# m901-vu-meter.net
KiCad netlist of a schematic drawn in EAGLE
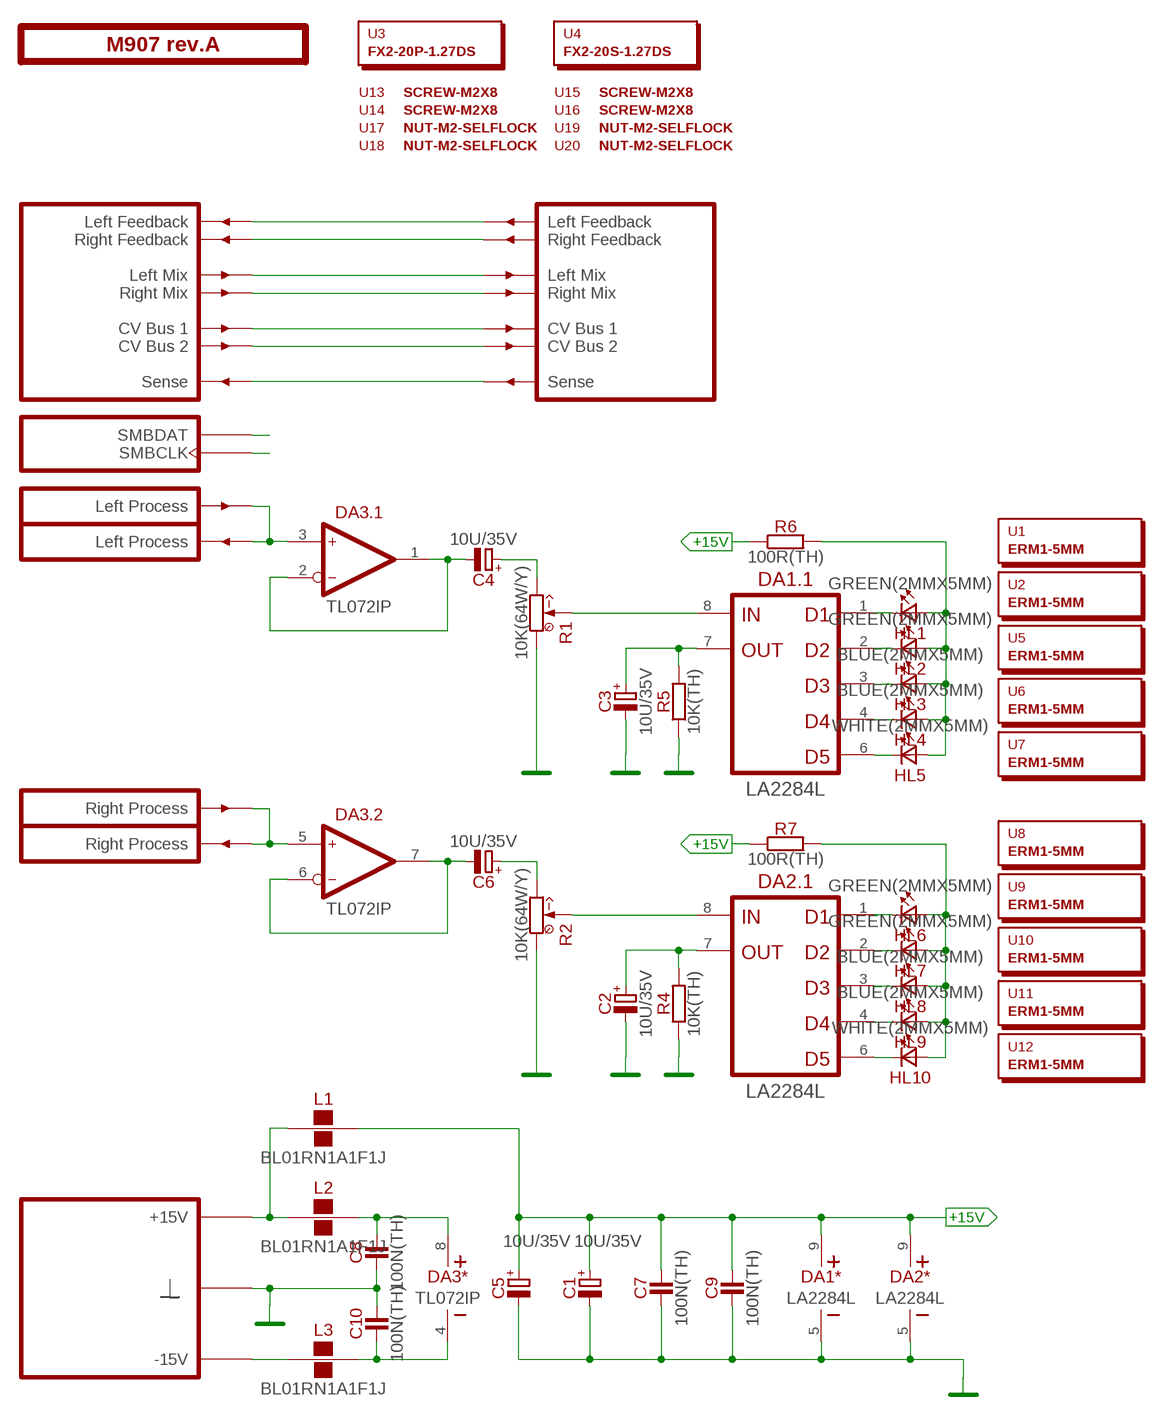
[diagram p0: schematic, sheet 1]

(export (version "E")
  (design (tool "Eeschema 10.0.6"))
  (components
    (comp (ref "C1")
      (value "10U/35V")
      (footprint "eagle-import:E2-5")
      (libsource (lib "eagle-import") (part "?10U/35V"))
    )
    (comp (ref "C2")
      (value "10U/35V")
      (footprint "eagle-import:E2-5")
      (libsource (lib "eagle-import") (part "?10U/35V"))
    )
    (comp (ref "C3")
      (value "10U/35V")
      (footprint "eagle-import:E2-5")
      (libsource (lib "eagle-import") (part "?10U/35V"))
    )
    (comp (ref "C4")
      (value "10U/35V")
      (footprint "eagle-import:E2-5")
      (libsource (lib "eagle-import") (part "?10U/35V"))
    )
    (comp (ref "C5")
      (value "10U/35V")
      (footprint "eagle-import:E2-5")
      (libsource (lib "eagle-import") (part "?10U/35V"))
    )
    (comp (ref "C6")
      (value "10U/35V")
      (footprint "eagle-import:E2-5")
      (libsource (lib "eagle-import") (part "?10U/35V"))
    )
    (comp (ref "C7")
      (value "100N(TH)")
      (footprint "eagle-import:C050-024X044")
      (libsource (lib "eagle-import") (part "?100N(TH)"))
    )
    (comp (ref "C8")
      (value "100N(TH)")
      (footprint "eagle-import:C050-024X044")
      (libsource (lib "eagle-import") (part "?100N(TH)"))
    )
    (comp (ref "C9")
      (value "100N(TH)")
      (footprint "eagle-import:C050-024X044")
      (libsource (lib "eagle-import") (part "?100N(TH)"))
    )
    (comp (ref "C10")
      (value "100N(TH)")
      (footprint "eagle-import:C050-024X044")
      (libsource (lib "eagle-import") (part "?100N(TH)"))
    )
    (comp (ref "DA1")
      (value "LA2284L")
      (footprint "eagle-import:SIL9")
      (libsource (lib "eagle-import") (part "LA2284L"))
    )
    (comp (ref "DA2")
      (value "LA2284L")
      (footprint "eagle-import:SIL9")
      (libsource (lib "eagle-import") (part "LA2284L"))
    )
    (comp (ref "DA3")
      (value "TL072IP")
      (footprint "eagle-import:DIP-8")
      (libsource (lib "eagle-import") (part "TL072IP"))
    )
    (comp (ref "HL1")
      (value "GREEN(2MMX5MM)")
      (footprint "eagle-import:LED2X5")
      (libsource (lib "eagle-import") (part "?(2MMX5MM)GREEN"))
    )
    (comp (ref "HL2")
      (value "GREEN(2MMX5MM)")
      (footprint "eagle-import:LED2X5")
      (libsource (lib "eagle-import") (part "?(2MMX5MM)GREEN"))
    )
    (comp (ref "HL3")
      (value "BLUE(2MMX5MM)")
      (footprint "eagle-import:LED2X5")
      (libsource (lib "eagle-import") (part "?(2MMX5MM)BLUE"))
    )
    (comp (ref "HL4")
      (value "BLUE(2MMX5MM)")
      (footprint "eagle-import:LED2X5")
      (libsource (lib "eagle-import") (part "?(2MMX5MM)BLUE"))
    )
    (comp (ref "HL5")
      (value "WHITE(2MMX5MM)")
      (footprint "eagle-import:LED2X5")
      (libsource (lib "eagle-import") (part "?(2MMX5MM)WHITE"))
    )
    (comp (ref "HL6")
      (value "GREEN(2MMX5MM)")
      (footprint "eagle-import:LED2X5")
      (libsource (lib "eagle-import") (part "?(2MMX5MM)GREEN"))
    )
    (comp (ref "HL7")
      (value "GREEN(2MMX5MM)")
      (footprint "eagle-import:LED2X5")
      (libsource (lib "eagle-import") (part "?(2MMX5MM)GREEN"))
    )
    (comp (ref "HL8")
      (value "BLUE(2MMX5MM)")
      (footprint "eagle-import:LED2X5")
      (libsource (lib "eagle-import") (part "?(2MMX5MM)BLUE"))
    )
    (comp (ref "HL9")
      (value "BLUE(2MMX5MM)")
      (footprint "eagle-import:LED2X5")
      (libsource (lib "eagle-import") (part "?(2MMX5MM)BLUE"))
    )
    (comp (ref "HL10")
      (value "WHITE(2MMX5MM)")
      (footprint "eagle-import:LED2X5")
      (libsource (lib "eagle-import") (part "?(2MMX5MM)WHITE"))
    )
    (comp (ref "L1")
      (value "BL01RN1A1F1J")
      (footprint "eagle-import:BL01RN1A")
      (libsource (lib "eagle-import") (part "BL01RN1A?1F1J"))
    )
    (comp (ref "L2")
      (value "BL01RN1A1F1J")
      (footprint "eagle-import:BL01RN1A")
      (libsource (lib "eagle-import") (part "BL01RN1A?1F1J"))
    )
    (comp (ref "L3")
      (value "BL01RN1A1F1J")
      (footprint "eagle-import:BL01RN1A")
      (libsource (lib "eagle-import") (part "BL01RN1A?1F1J"))
    )
    (comp (ref "PCB1")
      (value "M907 rev.A")
      (footprint "eagle-import:ST2-BOARD-26")
      (libsource (lib "eagle-import") (part "ST2-BOARD-?26"))
    )
    (comp (ref "R1")
      (value "10K(64W/Y)")
      (footprint "eagle-import:64W")
      (libsource (lib "eagle-import") (part "?(64W/Y)10K"))
    )
    (comp (ref "R2")
      (value "10K(64W/Y)")
      (footprint "eagle-import:64W")
      (libsource (lib "eagle-import") (part "?(64W/Y)10K"))
    )
    (comp (ref "R4")
      (value "10K(TH)")
      (footprint "eagle-import:R-0207_10")
      (libsource (lib "eagle-import") (part "?10K(TH)"))
    )
    (comp (ref "R5")
      (value "10K(TH)")
      (footprint "eagle-import:R-0207_10")
      (libsource (lib "eagle-import") (part "?10K(TH)"))
    )
    (comp (ref "R6")
      (value "100R(TH)")
      (footprint "eagle-import:R-0207_10")
      (libsource (lib "eagle-import") (part "?100R(TH)"))
    )
    (comp (ref "R7")
      (value "100R(TH)")
      (footprint "eagle-import:R-0207_10")
      (libsource (lib "eagle-import") (part "?100R(TH)"))
    )
    (comp (ref "U1")
      (value "ERM1-5MM")
      (footprint "eagle-import:EMPTY")
      (libsource (lib "eagle-import") (part "?ERM1-5MM"))
    )
    (comp (ref "U2")
      (value "ERM1-5MM")
      (footprint "eagle-import:EMPTY")
      (libsource (lib "eagle-import") (part "?ERM1-5MM"))
    )
    (comp (ref "U3")
      (value "FX2-20P-1.27DS")
      (footprint "eagle-import:EMPTY")
      (libsource (lib "eagle-import") (part "?FX2-20P-1.27DS"))
    )
    (comp (ref "U4")
      (value "FX2-20S-1.27DS")
      (footprint "eagle-import:EMPTY")
      (libsource (lib "eagle-import") (part "?FX2-20S-1.27DS"))
    )
    (comp (ref "U5")
      (value "ERM1-5MM")
      (footprint "eagle-import:EMPTY")
      (libsource (lib "eagle-import") (part "?ERM1-5MM"))
    )
    (comp (ref "U6")
      (value "ERM1-5MM")
      (footprint "eagle-import:EMPTY")
      (libsource (lib "eagle-import") (part "?ERM1-5MM"))
    )
    (comp (ref "U7")
      (value "ERM1-5MM")
      (footprint "eagle-import:EMPTY")
      (libsource (lib "eagle-import") (part "?ERM1-5MM"))
    )
    (comp (ref "U8")
      (value "ERM1-5MM")
      (footprint "eagle-import:EMPTY")
      (libsource (lib "eagle-import") (part "?ERM1-5MM"))
    )
    (comp (ref "U9")
      (value "ERM1-5MM")
      (footprint "eagle-import:EMPTY")
      (libsource (lib "eagle-import") (part "?ERM1-5MM"))
    )
    (comp (ref "U10")
      (value "ERM1-5MM")
      (footprint "eagle-import:EMPTY")
      (libsource (lib "eagle-import") (part "?ERM1-5MM"))
    )
    (comp (ref "U11")
      (value "ERM1-5MM")
      (footprint "eagle-import:EMPTY")
      (libsource (lib "eagle-import") (part "?ERM1-5MM"))
    )
    (comp (ref "U12")
      (value "ERM1-5MM")
      (footprint "eagle-import:EMPTY")
      (libsource (lib "eagle-import") (part "?ERM1-5MM"))
    )
    (comp (ref "U13")
      (value "SCREW-M2X8")
      (footprint "eagle-import:EMPTY")
      (libsource (lib "eagle-import") (part "?SCREW-M2X8"))
    )
    (comp (ref "U14")
      (value "SCREW-M2X8")
      (footprint "eagle-import:EMPTY")
      (libsource (lib "eagle-import") (part "?SCREW-M2X8"))
    )
    (comp (ref "U15")
      (value "SCREW-M2X8")
      (footprint "eagle-import:EMPTY")
      (libsource (lib "eagle-import") (part "?SCREW-M2X8"))
    )
    (comp (ref "U16")
      (value "SCREW-M2X8")
      (footprint "eagle-import:EMPTY")
      (libsource (lib "eagle-import") (part "?SCREW-M2X8"))
    )
    (comp (ref "U17")
      (value "NUT-M2-SELFLOCK")
      (footprint "eagle-import:EMPTY")
      (libsource (lib "eagle-import") (part "?NUT-M2-SELFLOCK"))
    )
    (comp (ref "U18")
      (value "NUT-M2-SELFLOCK")
      (footprint "eagle-import:EMPTY")
      (libsource (lib "eagle-import") (part "?NUT-M2-SELFLOCK"))
    )
    (comp (ref "U19")
      (value "NUT-M2-SELFLOCK")
      (footprint "eagle-import:EMPTY")
      (libsource (lib "eagle-import") (part "?NUT-M2-SELFLOCK"))
    )
    (comp (ref "U20")
      (value "NUT-M2-SELFLOCK")
      (footprint "eagle-import:EMPTY")
      (libsource (lib "eagle-import") (part "?NUT-M2-SELFLOCK"))
    )
  )
  (nets
    (net (code "1") (name "+15V") (class "Default")
      (node (ref "C1") (pin "+") (pinfunction "+_+") (pintype "passive"))
      (node (ref "C5") (pin "+") (pinfunction "+_+") (pintype "passive"))
      (node (ref "C7") (pin "2") (pinfunction "2_2") (pintype "passive"))
      (node (ref "C9") (pin "2") (pinfunction "2_2") (pintype "passive"))
      (node (ref "DA1") (pin "9") (pinfunction "V+_9") (pintype "power_in"))
      (node (ref "DA2") (pin "9") (pinfunction "V+_9") (pintype "power_in"))
      (node (ref "L1") (pin "2") (pinfunction "2_2") (pintype "passive"))
      (node (ref "R6") (pin "1") (pinfunction "1_1") (pintype "passive"))
      (node (ref "R7") (pin "1") (pinfunction "1_1") (pintype "passive"))
    )
    (net (code "2") (name "GND") (class "Default")
      (node (ref "C1") (pin "-") (pinfunction "-_-") (pintype "passive"))
      (node (ref "C10") (pin "2") (pinfunction "2_2") (pintype "passive"))
      (node (ref "C2") (pin "-") (pinfunction "-_-") (pintype "passive"))
      (node (ref "C3") (pin "-") (pinfunction "-_-") (pintype "passive"))
      (node (ref "C5") (pin "-") (pinfunction "-_-") (pintype "passive"))
      (node (ref "C7") (pin "1") (pinfunction "1_1") (pintype "passive"))
      (node (ref "C8") (pin "1") (pinfunction "1_1") (pintype "passive"))
      (node (ref "C9") (pin "1") (pinfunction "1_1") (pintype "passive"))
      (node (ref "DA1") (pin "5") (pinfunction "V-_5") (pintype "power_in"))
      (node (ref "DA2") (pin "5") (pinfunction "V-_5") (pintype "power_in"))
      (node (ref "PCB1") (pin "B4") (pinfunction "GND_B4") (pintype "bidirectional"))
      (node (ref "PCB1") (pin "B4'") (pinfunction "GND_B4'") (pintype "bidirectional"))
      (node (ref "PCB1") (pin "B5") (pinfunction "GND_B5") (pintype "bidirectional"))
      (node (ref "PCB1") (pin "B5'") (pinfunction "GND_B5'") (pintype "bidirectional"))
      (node (ref "PCB1") (pin "B6") (pinfunction "GND_B6") (pintype "bidirectional"))
      (node (ref "PCB1") (pin "B6'") (pinfunction "GND_B6'") (pintype "bidirectional"))
      (node (ref "PCB1") (pin "B7") (pinfunction "GND_B7") (pintype "bidirectional"))
      (node (ref "PCB1") (pin "B7'") (pinfunction "GND_B7'") (pintype "bidirectional"))
      (node (ref "PCB1") (pin "B8") (pinfunction "GND_B8") (pintype "bidirectional"))
      (node (ref "PCB1") (pin "B8'") (pinfunction "GND_B8'") (pintype "bidirectional"))
      (node (ref "R1") (pin "1") (pinfunction "CCW_1") (pintype "passive"))
      (node (ref "R2") (pin "1") (pinfunction "CCW_1") (pintype "passive"))
      (node (ref "R4") (pin "1") (pinfunction "1_1") (pintype "passive"))
      (node (ref "R5") (pin "1") (pinfunction "1_1") (pintype "passive"))
    )
    (net (code "3") (name "Net-(DA1B-D1)") (class "Default")
      (node (ref "DA1") (pin "1") (pinfunction "D1_1") (pintype "input"))
      (node (ref "HL1") (pin "K") (pinfunction "C_K") (pintype "passive"))
    )
    (net (code "4") (name "Net-(DA1B-D2)") (class "Default")
      (node (ref "DA1") (pin "2") (pinfunction "D2_2") (pintype "input"))
      (node (ref "HL2") (pin "K") (pinfunction "C_K") (pintype "passive"))
    )
    (net (code "5") (name "Net-(DA1B-D3)") (class "Default")
      (node (ref "DA1") (pin "3") (pinfunction "D3_3") (pintype "input"))
      (node (ref "HL3") (pin "K") (pinfunction "C_K") (pintype "passive"))
    )
    (net (code "6") (name "Net-(DA1B-D4)") (class "Default")
      (node (ref "DA1") (pin "4") (pinfunction "D4_4") (pintype "input"))
      (node (ref "HL4") (pin "K") (pinfunction "C_K") (pintype "passive"))
    )
    (net (code "7") (name "Net-(DA1B-D5)") (class "Default")
      (node (ref "DA1") (pin "6") (pinfunction "D5_6") (pintype "input"))
      (node (ref "HL5") (pin "K") (pinfunction "C_K") (pintype "passive"))
    )
    (net (code "8") (name "Net-(DA1B-IN)") (class "Default")
      (node (ref "DA1") (pin "8") (pinfunction "IN_8") (pintype "input"))
      (node (ref "R1") (pin "S") (pinfunction "W_S") (pintype "passive"))
      (node (ref "R1") (pin "S@1") (pinfunction "W_S@1") (pintype "passive"))
    )
    (net (code "9") (name "Net-(DA1B-OUT)") (class "Default")
      (node (ref "C3") (pin "+") (pinfunction "+_+") (pintype "passive"))
      (node (ref "DA1") (pin "7") (pinfunction "OUT_7") (pintype "input"))
      (node (ref "R5") (pin "2") (pinfunction "2_2") (pintype "passive"))
    )
    (net (code "10") (name "Net-(DA2B-D1)") (class "Default")
      (node (ref "DA2") (pin "1") (pinfunction "D1_1") (pintype "input"))
      (node (ref "HL6") (pin "K") (pinfunction "C_K") (pintype "passive"))
    )
    (net (code "11") (name "Net-(DA2B-D2)") (class "Default")
      (node (ref "DA2") (pin "2") (pinfunction "D2_2") (pintype "input"))
      (node (ref "HL7") (pin "K") (pinfunction "C_K") (pintype "passive"))
    )
    (net (code "12") (name "Net-(DA2B-D3)") (class "Default")
      (node (ref "DA2") (pin "3") (pinfunction "D3_3") (pintype "input"))
      (node (ref "HL8") (pin "K") (pinfunction "C_K") (pintype "passive"))
    )
    (net (code "13") (name "Net-(DA2B-D4)") (class "Default")
      (node (ref "DA2") (pin "4") (pinfunction "D4_4") (pintype "input"))
      (node (ref "HL9") (pin "K") (pinfunction "C_K") (pintype "passive"))
    )
    (net (code "14") (name "Net-(DA2B-D5)") (class "Default")
      (node (ref "DA2") (pin "6") (pinfunction "D5_6") (pintype "input"))
      (node (ref "HL10") (pin "K") (pinfunction "C_K") (pintype "passive"))
    )
    (net (code "15") (name "Net-(DA2B-IN)") (class "Default")
      (node (ref "DA2") (pin "8") (pinfunction "IN_8") (pintype "input"))
      (node (ref "R2") (pin "S") (pinfunction "W_S") (pintype "passive"))
      (node (ref "R2") (pin "S@1") (pinfunction "W_S@1") (pintype "passive"))
    )
    (net (code "16") (name "Net-(DA2B-OUT)") (class "Default")
      (node (ref "C2") (pin "+") (pinfunction "+_+") (pintype "passive"))
      (node (ref "DA2") (pin "7") (pinfunction "OUT_7") (pintype "input"))
      (node (ref "R4") (pin "2") (pinfunction "2_2") (pintype "passive"))
    )
    (net (code "17") (name "Net-(DA3A-V+)") (class "Default")
      (node (ref "C8") (pin "2") (pinfunction "2_2") (pintype "passive"))
      (node (ref "DA3") (pin "8") (pinfunction "V+_8") (pintype "power_in"))
      (node (ref "L2") (pin "2") (pinfunction "2_2") (pintype "passive"))
    )
    (net (code "18") (name "Net-(DA3A-V-)") (class "Default")
      (node (ref "C10") (pin "1") (pinfunction "1_1") (pintype "passive"))
      (node (ref "DA3") (pin "4") (pinfunction "V-_4") (pintype "power_in"))
      (node (ref "L3") (pin "2") (pinfunction "2_2") (pintype "passive"))
    )
    (net (code "19") (name "Net-(DA3B-IN+)") (class "Default")
      (node (ref "DA3") (pin "3") (pinfunction "IN+_3") (pintype "input"))
      (node (ref "PCB1") (pin "BINL") (pinfunction "INL_BINL") (pintype "bidirectional"))
      (node (ref "PCB1") (pin "BOUTL'") (pinfunction "OUTL_BOUTL'") (pintype "bidirectional"))
    )
    (net (code "20") (name "Net-(DA3B-IN-)") (class "Default")
      (node (ref "C4") (pin "-") (pinfunction "-_-") (pintype "passive"))
      (node (ref "DA3") (pin "1") (pinfunction "OUT_1") (pintype "output"))
      (node (ref "DA3") (pin "2") (pinfunction "IN-_2") (pintype "input"))
    )
    (net (code "21") (name "Net-(DA3C-IN+)") (class "Default")
      (node (ref "DA3") (pin "5") (pinfunction "IN+_5") (pintype "input"))
      (node (ref "PCB1") (pin "BINR") (pinfunction "INR_BINR") (pintype "bidirectional"))
      (node (ref "PCB1") (pin "BOUTR'") (pinfunction "OUTR_BOUTR'") (pintype "bidirectional"))
    )
    (net (code "22") (name "Net-(DA3C-IN-)") (class "Default")
      (node (ref "C6") (pin "-") (pinfunction "-_-") (pintype "passive"))
      (node (ref "DA3") (pin "6") (pinfunction "IN-_6") (pintype "input"))
      (node (ref "DA3") (pin "7") (pinfunction "OUT_7") (pintype "output"))
    )
    (net (code "23") (name "Net-(HL1-PadA)") (class "Default")
      (node (ref "HL1") (pin "A") (pinfunction "A_A") (pintype "passive"))
      (node (ref "HL2") (pin "A") (pinfunction "A_A") (pintype "passive"))
      (node (ref "HL3") (pin "A") (pinfunction "A_A") (pintype "passive"))
      (node (ref "HL4") (pin "A") (pinfunction "A_A") (pintype "passive"))
      (node (ref "HL5") (pin "A") (pinfunction "A_A") (pintype "passive"))
      (node (ref "R6") (pin "2") (pinfunction "2_2") (pintype "passive"))
    )
    (net (code "24") (name "Net-(HL10-PadA)") (class "Default")
      (node (ref "HL10") (pin "A") (pinfunction "A_A") (pintype "passive"))
      (node (ref "HL6") (pin "A") (pinfunction "A_A") (pintype "passive"))
      (node (ref "HL7") (pin "A") (pinfunction "A_A") (pintype "passive"))
      (node (ref "HL8") (pin "A") (pinfunction "A_A") (pintype "passive"))
      (node (ref "HL9") (pin "A") (pinfunction "A_A") (pintype "passive"))
      (node (ref "R7") (pin "2") (pinfunction "2_2") (pintype "passive"))
    )
    (net (code "25") (name "Net-(L1-Pad1)") (class "Default")
      (node (ref "L1") (pin "1") (pinfunction "1_1") (pintype "passive"))
      (node (ref "L2") (pin "1") (pinfunction "1_1") (pintype "passive"))
      (node (ref "PCB1") (pin "A+15") (pinfunction "P+15V_A+15") (pintype "bidirectional"))
      (node (ref "PCB1") (pin "A+15'") (pinfunction "P+15V_A+15'") (pintype "bidirectional"))
      (node (ref "PCB1") (pin "B+15") (pinfunction "P+15V_B+15") (pintype "bidirectional"))
      (node (ref "PCB1") (pin "B+15'") (pinfunction "P+15V_B+15'") (pintype "bidirectional"))
    )
    (net (code "26") (name "Net-(L3-Pad1)") (class "Default")
      (node (ref "L3") (pin "1") (pinfunction "1_1") (pintype "passive"))
      (node (ref "PCB1") (pin "A-15") (pinfunction "P-15V_A-15") (pintype "bidirectional"))
      (node (ref "PCB1") (pin "A-15'") (pinfunction "P-15V_A-15'") (pintype "bidirectional"))
      (node (ref "PCB1") (pin "B-15") (pinfunction "P-15V_B-15") (pintype "bidirectional"))
      (node (ref "PCB1") (pin "B-15'") (pinfunction "P-15V_B-15'") (pintype "bidirectional"))
    )
    (net (code "27") (name "Net-(PCB1F-CV1)") (class "Default")
      (node (ref "PCB1") (pin "ACV1") (pinfunction "CV1_ACV1") (pintype "bidirectional"))
      (node (ref "PCB1") (pin "ACV1'") (pinfunction "CV1'_ACV1'") (pintype "bidirectional"))
    )
    (net (code "28") (name "Net-(PCB1F-CV2)") (class "Default")
      (node (ref "PCB1") (pin "ACV2") (pinfunction "CV2_ACV2") (pintype "bidirectional"))
      (node (ref "PCB1") (pin "ACV2'") (pinfunction "CV2'_ACV2'") (pintype "bidirectional"))
    )
    (net (code "29") (name "Net-(PCB1F-LFBK)") (class "Default")
      (node (ref "PCB1") (pin "ALFBK") (pinfunction "LFBK_ALFBK") (pintype "bidirectional"))
      (node (ref "PCB1") (pin "ALFBK'") (pinfunction "LFBK'_ALFBK'") (pintype "bidirectional"))
    )
    (net (code "30") (name "Net-(PCB1F-LMIX)") (class "Default")
      (node (ref "PCB1") (pin "ALMIX") (pinfunction "LMIX_ALMIX") (pintype "bidirectional"))
      (node (ref "PCB1") (pin "ALMIX'") (pinfunction "LMIX'_ALMIX'") (pintype "bidirectional"))
    )
    (net (code "31") (name "Net-(PCB1F-RFBK)") (class "Default")
      (node (ref "PCB1") (pin "ARFBK") (pinfunction "RFBK_ARFBK") (pintype "bidirectional"))
      (node (ref "PCB1") (pin "ARFBK'") (pinfunction "RFBK'_ARFBK'") (pintype "bidirectional"))
    )
    (net (code "32") (name "Net-(PCB1F-RMIX)") (class "Default")
      (node (ref "PCB1") (pin "ARMIX") (pinfunction "RMIX_ARMIX") (pintype "bidirectional"))
      (node (ref "PCB1") (pin "ARMIX'") (pinfunction "RMIX'_ARMIX'") (pintype "bidirectional"))
    )
    (net (code "33") (name "Net-(PCB1F-SENSE)") (class "Default")
      (node (ref "PCB1") (pin "BSENSE") (pinfunction "SENSE_BSENSE") (pintype "bidirectional"))
      (node (ref "PCB1") (pin "BSENSE'") (pinfunction "SENSE'_BSENSE'") (pintype "bidirectional"))
    )
    (net (code "34") (name "Net-(PCB1H-SMBCLK-PadASMBCLK')") (class "Default")
      (node (ref "PCB1") (pin "ASMBCLK") (pinfunction "SMBCLK_ASMBCLK") (pintype "bidirectional"))
      (node (ref "PCB1") (pin "ASMBCLK'") (pinfunction "SMBCLK_ASMBCLK'") (pintype "bidirectional"))
    )
    (net (code "35") (name "Net-(PCB1H-SMBDAT-PadASMBDAT')") (class "Default")
      (node (ref "PCB1") (pin "ASMBDAT") (pinfunction "SMBDAT_ASMBDAT") (pintype "bidirectional"))
      (node (ref "PCB1") (pin "ASMBDAT'") (pinfunction "SMBDAT_ASMBDAT'") (pintype "bidirectional"))
    )
    (net (code "36") (name "Net-(R1-CW)") (class "Default")
      (node (ref "C4") (pin "+") (pinfunction "+_+") (pintype "passive"))
      (node (ref "R1") (pin "3") (pinfunction "CW_3") (pintype "passive"))
    )
    (net (code "37") (name "Net-(R2-CW)") (class "Default")
      (node (ref "C6") (pin "+") (pinfunction "+_+") (pintype "passive"))
      (node (ref "R2") (pin "3") (pinfunction "CW_3") (pintype "passive"))
    )
  )
)
